# FINAL_YEAR_PROJECT.net
KiCad netlist of a schematic drawn in EasyEDA
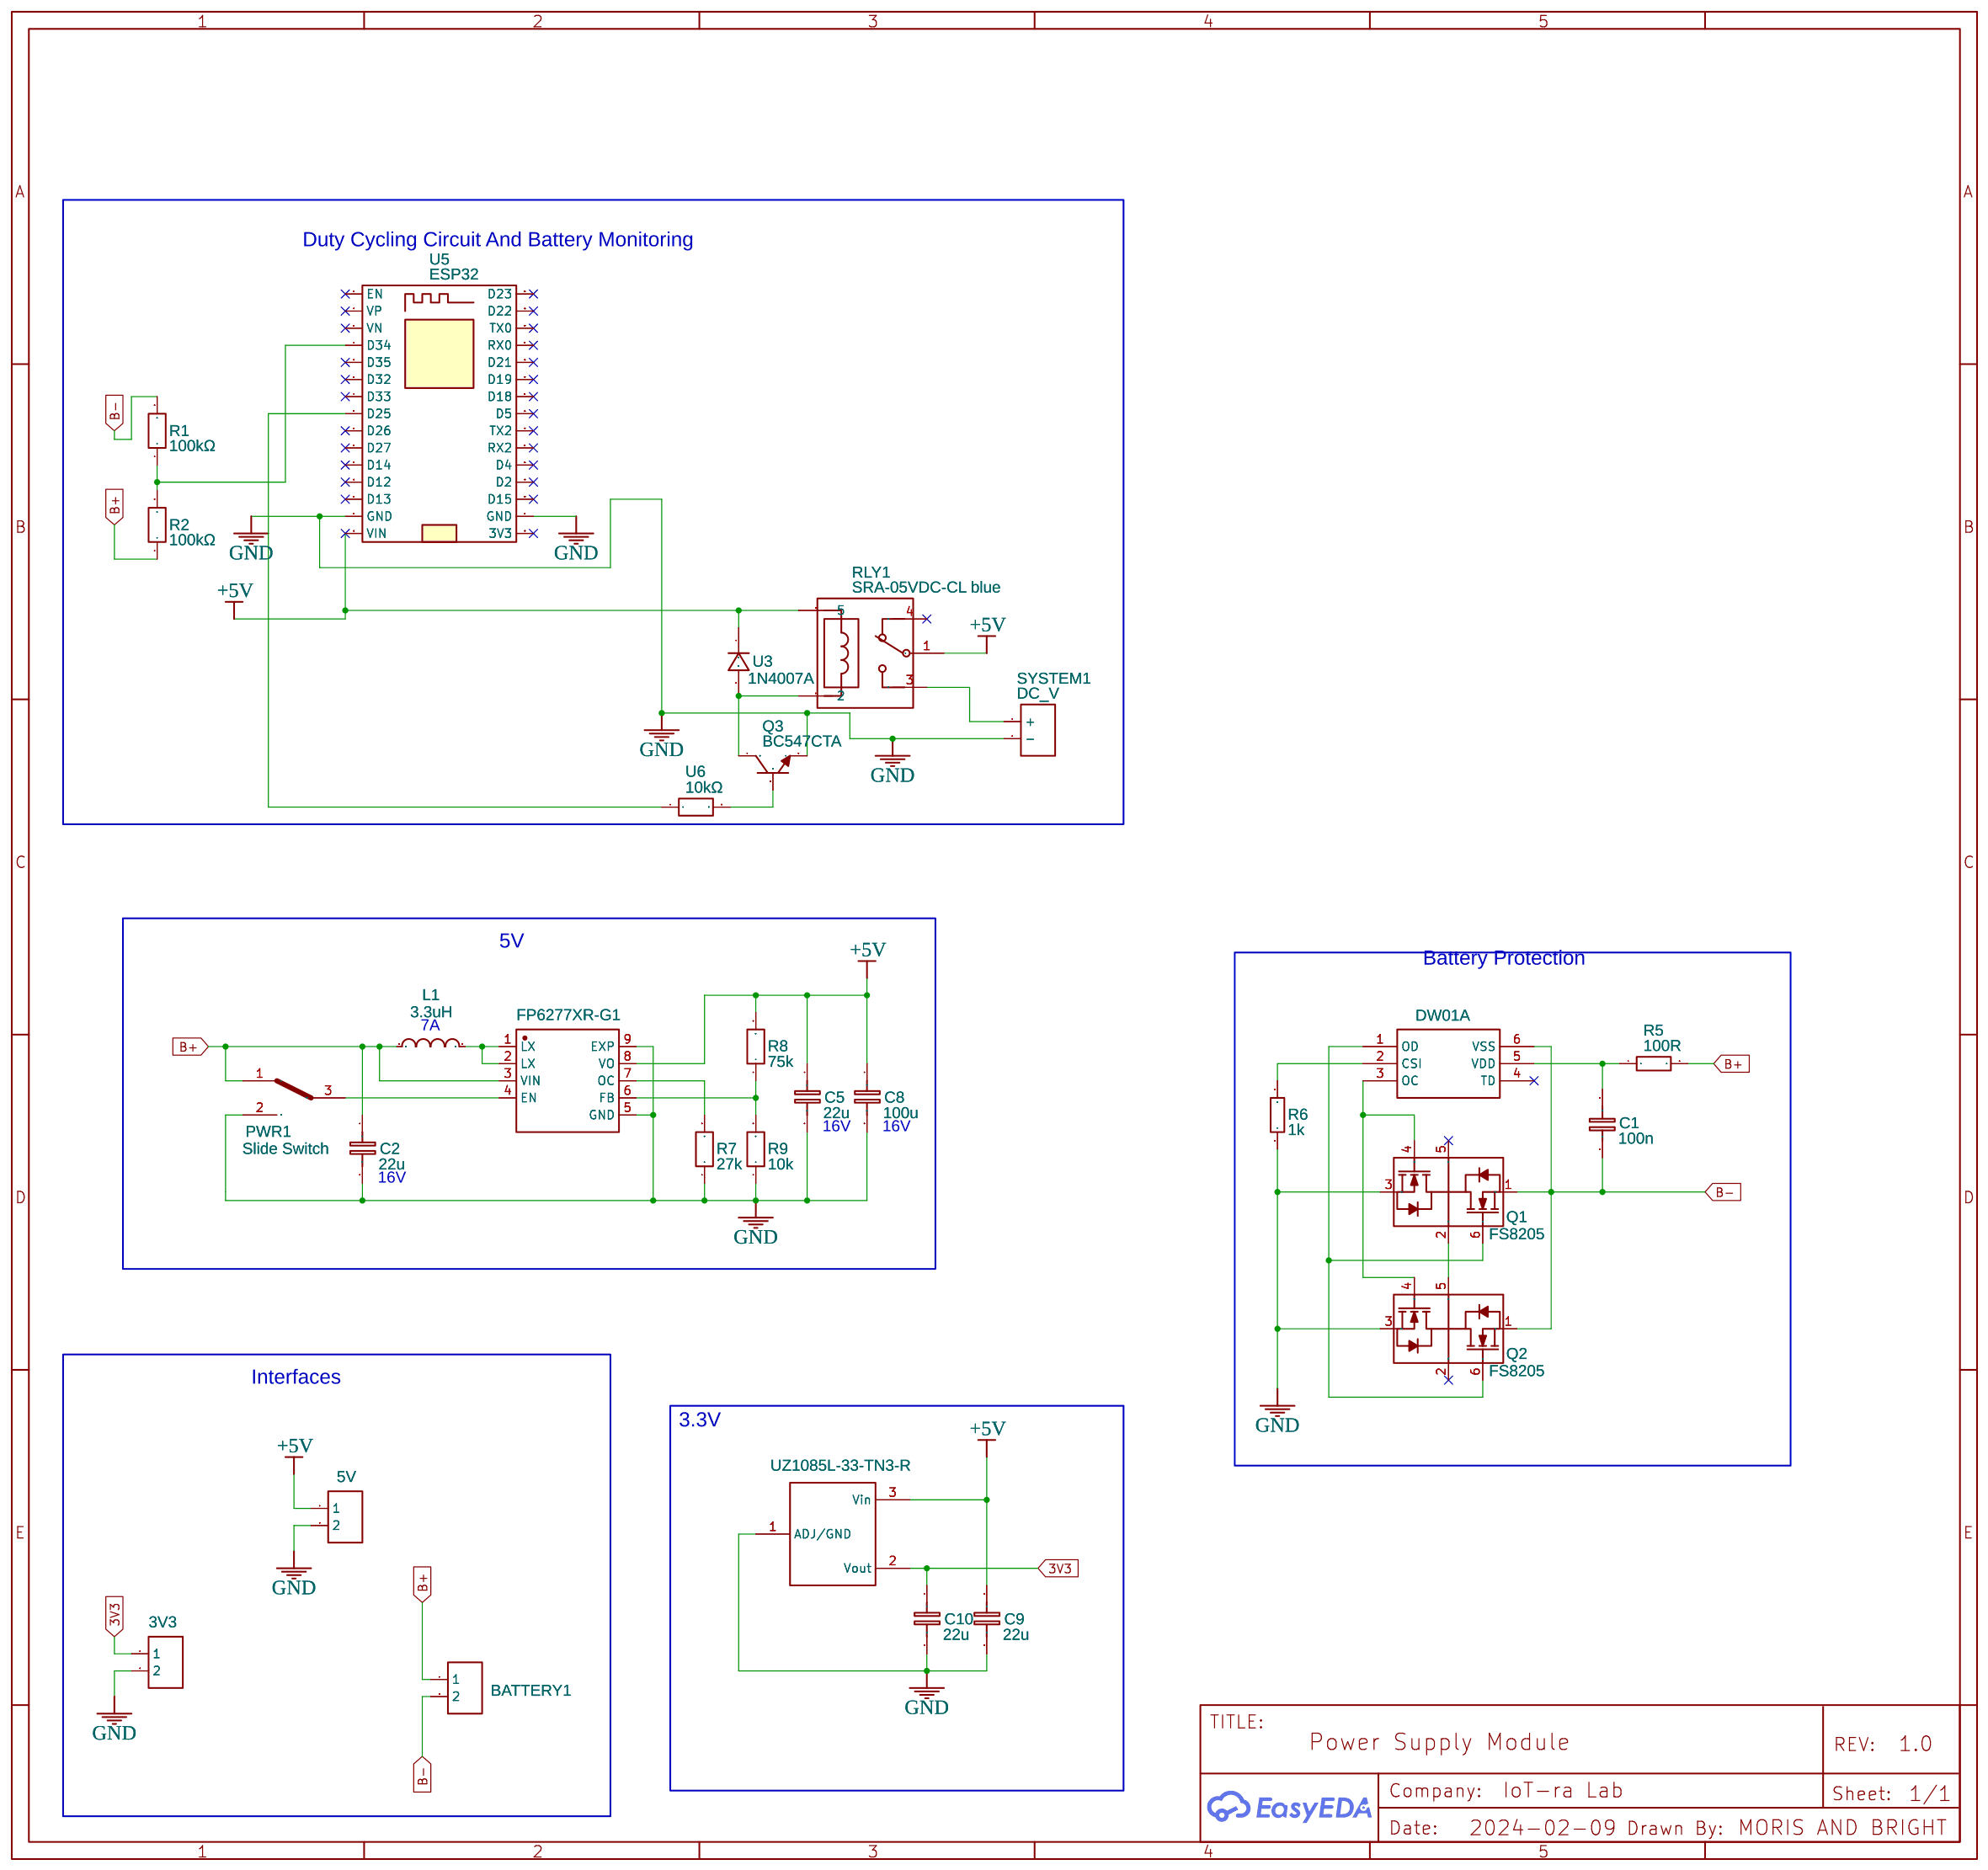
[diagram p0: schematic sheet]

(export (version "E")
  (design (tool "Eeschema 10.0.6"))
  (components
    (comp (ref "3V3")
      (value "Connector")
      (fields (field (name "Manufacturer Part") "2.54-1*2PFemale") (field (name "Manufacturer") "BOOMELE"))
      (libsource (lib "") (part "Unknown_80_-110"))
    )
    (comp (ref "5V")
      (value "Connector")
      (fields (field (name "Manufacturer Part") "2.54-1*2PFemale") (field (name "Manufacturer") "BOOMELE"))
      (libsource (lib "") (part "Unknown_185_-195"))
    )
    (comp (ref "BATTERY1")
      (value "Connector")
      (fields (field (name "Manufacturer Part") "2.54-1*2PFemale") (field (name "Manufacturer") "BOOMELE"))
      (libsource (lib "") (part "Unknown_255_-95"))
    )
    (comp (ref "C1")
      (value "100n")
      (fields (field (name "Manufacturer Part") "CC0805KRX7R9BB104") (field (name "Manufacturer") "YAGEO"))
      (libsource (lib "") (part "Cap_0805_EU_2"))
    )
    (comp (ref "C2")
      (value "22u")
      (fields (field (name "Manufacturer Part") "CL21A226MAQNNNE") (field (name "Manufacturer") "SAMSUNG"))
      (libsource (lib "") (part "Cap_0805_EU"))
    )
    (comp (ref "C5")
      (value "22u")
      (fields (field (name "Manufacturer Part") "CL21A226MAQNNNE") (field (name "Manufacturer") "SAMSUNG"))
      (libsource (lib "") (part "Cap_0805_EU"))
    )
    (comp (ref "C8")
      (value "100u")
      (fields (field (name "Manufacturer Part") "CL31A107MPHNNNE") (field (name "Manufacturer") "SAMSUNG"))
      (libsource (lib "") (part "Cap_0805_EU"))
    )
    (comp (ref "C9")
      (value "22u")
      (fields (field (name "Manufacturer Part") "CL21A226MAQNNNE") (field (name "Manufacturer") "SAMSUNG"))
      (libsource (lib "") (part "Cap_0805_EU_1"))
    )
    (comp (ref "C10")
      (value "22u")
      (fields (field (name "Manufacturer Part") "CL21A226MAQNNNE") (field (name "Manufacturer") "SAMSUNG"))
      (libsource (lib "") (part "Cap_0805_EU_1"))
    )
    (comp (ref "L1")
      (value "3.3uH")
      (fields (field (name "Manufacturer Part") "JSHC0650H-3R3M-G") (field (name "Manufacturer") "Jinlai"))
      (libsource (lib "") (part "JSHC0650H-3R3M-G"))
    )
    (comp (ref "PWR1")
      (value "Slide Switch")
      (fields (field (name "Manufacturer Part") "New SchematicLib"))
      (libsource (lib "") (part "Unknown_160_-440"))
    )
    (comp (ref "Q1")
      (value "FS8205")
      (fields (field (name "Manufacturer") "FORTUNE"))
      (libsource (lib "") (part "FS8205"))
    )
    (comp (ref "Q2")
      (value "FS8205")
      (fields (field (name "Manufacturer") "FORTUNE"))
      (libsource (lib "") (part "FS8205"))
    )
    (comp (ref "Q3")
      (value "BC547CTA")
      (fields (field (name "Manufacturer") "onsemi(安森美)"))
      (libsource (lib "") (part "BC547CTA"))
    )
    (comp (ref "R1")
      (value "100kΩ")
      (fields
        (field (name "Manufacturer Part") "RNF14FAE100K")
        (field (name "Manufacturer") "SEI(Stackpole Electronics Inc.)")
      )
      (libsource (lib "") (part "RNF14FAE100K"))
    )
    (comp (ref "R2")
      (value "100kΩ")
      (fields
        (field (name "Manufacturer Part") "RNF14FAE100K")
        (field (name "Manufacturer") "SEI(Stackpole Electronics Inc.)")
      )
      (libsource (lib "") (part "RNF14FAE100K"))
    )
    (comp (ref "R5")
      (value "100R")
      (fields (field (name "Manufacturer Part") "0805W8F1000T5E") (field (name "Manufacturer") "UniOhm"))
      (libsource (lib "") (part "Res_0805(1/8W)_EU_2"))
    )
    (comp (ref "R6")
      (value "1k")
      (fields (field (name "Manufacturer Part") "0805W8F1001T5E") (field (name "Manufacturer") "UniOhm"))
      (libsource (lib "") (part "Res_0805(1/8W)_EU_1"))
    )
    (comp (ref "R7")
      (value "27k")
      (fields (field (name "Manufacturer Part") "0805W8F2702T5E") (field (name "Manufacturer") "UniOhm"))
      (libsource (lib "") (part "Res_0805(1/8W)_EU"))
    )
    (comp (ref "R8")
      (value "75k")
      (fields (field (name "Manufacturer Part") "0805W8F7502T5E") (field (name "Manufacturer") "UniOhm"))
      (libsource (lib "") (part "Res_0805(1/8W)_EU"))
    )
    (comp (ref "R9")
      (value "10k")
      (fields (field (name "Manufacturer Part") "0805W8F1002T5E") (field (name "Manufacturer") "UniOhm"))
      (libsource (lib "") (part "Res_0805(1/8W)_EU"))
    )
    (comp (ref "RLY1")
      (value "SRA-05VDC-CL blue")
      (fields (field (name "Manufacturer Part") "SRA-05VDC-CL") (field (name "Manufacturer") "松乐"))
      (libsource (lib "") (part "SRA-05VDC-CL blue"))
    )
    (comp (ref "SYSTEM1") (value "DC_V") (libsource (lib "") (part "DC_V")))
    (comp (ref "U1")
      (value "FP6277XR-G1")
      (fields (field (name "Manufacturer") "Feeling Technology"))
      (libsource (lib "") (part "FP6277XR-G1"))
    )
    (comp (ref "U2")
      (value "DW01A")
      (fields (field (name "Manufacturer") "FM"))
      (libsource (lib "") (part "Unknown_835_-460"))
    )
    (comp (ref "U3")
      (value "1N4007A")
      (fields (field (name "Manufacturer") "LRC(乐山无线电)"))
      (libsource (lib "") (part "1N4007A"))
    )
    (comp (ref "U4")
      (value "UZ1085L-33-TN3-R")
      (fields (field (name "Manufacturer") "UTC"))
      (libsource (lib "") (part "UZ1085L-33-TN3-R"))
    )
    (comp (ref "U5") (value "ESP32") (libsource (lib "") (part "ESP32")))
    (comp (ref "U6")
      (value "10kΩ")
      (fields (field (name "Manufacturer Part") "FM0207FTE52-10K") (field (name "Manufacturer") "YAGEO(国巨)"))
      (libsource (lib "") (part "FM0207FTE52-10K"))
    )
  )
  (nets
    (net (code "1") (name "+5V") (class "Default")
      (node (ref "5V") (pin "1") (pinfunction "1_1") (pintype "input"))
      (node (ref "C5") (pin "1") (pinfunction "1_1") (pintype "unspecified"))
      (node (ref "C8") (pin "1") (pinfunction "1_1") (pintype "unspecified"))
      (node (ref "C9") (pin "1") (pinfunction "1_1") (pintype "unspecified"))
      (node (ref "R8") (pin "2") (pinfunction "2_2") (pintype "unspecified"))
      (node (ref "RLY1") (pin "1") (pinfunction "1_1") (pintype "unspecified"))
      (node (ref "RLY1") (pin "5") (pinfunction "5_5") (pintype "unspecified"))
      (node (ref "U1") (pin "8") (pinfunction "VO_8") (pintype "unspecified"))
      (node (ref "U3") (pin "1") (pinfunction "1_1") (pintype "unspecified"))
      (node (ref "U4") (pin "3") (pinfunction "Vin_3") (pintype "unspecified"))
      (node (ref "U5") (pin "15") (pinfunction "VIN_15") (pintype "unspecified"))
    )
    (net (code "2") (name "3V3") (class "Default")
      (node (ref "3V3") (pin "1") (pinfunction "1_1") (pintype "input"))
      (node (ref "C10") (pin "1") (pinfunction "1_1") (pintype "unspecified"))
      (node (ref "U4") (pin "2") (pinfunction "Vout_2") (pintype "unspecified"))
    )
    (net (code "3") (name "B+") (class "Default")
      (node (ref "BATTERY1") (pin "1") (pinfunction "1_1") (pintype "input"))
      (node (ref "C2") (pin "1") (pinfunction "1_1") (pintype "unspecified"))
      (node (ref "L1") (pin "1") (pinfunction "1_1") (pintype "unspecified"))
      (node (ref "PWR1") (pin "1") (pinfunction "1_1") (pintype "unspecified"))
      (node (ref "R2") (pin "1") (pinfunction "1_1") (pintype "unspecified"))
      (node (ref "R5") (pin "2") (pinfunction "2_2") (pintype "unspecified"))
      (node (ref "U1") (pin "3") (pinfunction "VIN_3") (pintype "unspecified"))
    )
    (net (code "4") (name "B-") (class "Default")
      (node (ref "BATTERY1") (pin "2") (pinfunction "2_2") (pintype "input"))
      (node (ref "C1") (pin "1") (pinfunction "1_1") (pintype "unspecified"))
      (node (ref "Q1") (pin "1") (pinfunction "S1_1") (pintype "unspecified"))
      (node (ref "Q2") (pin "1") (pinfunction "S1_1") (pintype "unspecified"))
      (node (ref "R1") (pin "2") (pinfunction "2_2") (pintype "unspecified"))
      (node (ref "U2") (pin "6") (pinfunction "VSS_6") (pintype "unspecified"))
    )
    (net (code "5") (name "GND") (class "Default")
      (node (ref "3V3") (pin "2") (pinfunction "2_2") (pintype "input"))
      (node (ref "5V") (pin "2") (pinfunction "2_2") (pintype "input"))
      (node (ref "C10") (pin "2") (pinfunction "2_2") (pintype "unspecified"))
      (node (ref "C2") (pin "2") (pinfunction "2_2") (pintype "unspecified"))
      (node (ref "C5") (pin "2") (pinfunction "2_2") (pintype "unspecified"))
      (node (ref "C8") (pin "2") (pinfunction "2_2") (pintype "unspecified"))
      (node (ref "C9") (pin "2") (pinfunction "2_2") (pintype "unspecified"))
      (node (ref "PWR1") (pin "2") (pinfunction "2_2") (pintype "unspecified"))
      (node (ref "Q1") (pin "3") (pinfunction "S2_3") (pintype "unspecified"))
      (node (ref "Q2") (pin "3") (pinfunction "S2_3") (pintype "unspecified"))
      (node (ref "Q3") (pin "3") (pinfunction "E_3") (pintype "input"))
      (node (ref "R6") (pin "1") (pinfunction "1_1") (pintype "unspecified"))
      (node (ref "R7") (pin "1") (pinfunction "1_1") (pintype "unspecified"))
      (node (ref "R9") (pin "1") (pinfunction "1_1") (pintype "unspecified"))
      (node (ref "SYSTEM1") (pin "2") (pinfunction "-_2") (pintype "unspecified"))
      (node (ref "U1") (pin "5") (pinfunction "GND_5") (pintype "unspecified"))
      (node (ref "U1") (pin "9") (pinfunction "EXP_9") (pintype "unspecified"))
      (node (ref "U4") (pin "1") (pinfunction "ADJ/GND_1") (pintype "unspecified"))
      (node (ref "U5") (pin "14") (pinfunction "GND_14") (pintype "unspecified"))
      (node (ref "U5") (pin "17") (pinfunction "GND_17") (pintype "unspecified"))
    )
    (net (code "6") (name "Net-(L1-Pad2)") (class "Default")
      (node (ref "L1") (pin "2") (pinfunction "2_2") (pintype "unspecified"))
      (node (ref "U1") (pin "1") (pinfunction "LX_1") (pintype "unspecified"))
      (node (ref "U1") (pin "2") (pinfunction "LX_2") (pintype "unspecified"))
    )
    (net (code "7") (name "Net-(Q1-D12-Pad2)") (class "Default")
      (node (ref "Q1") (pin "2") (pinfunction "D12_2") (pintype "unspecified"))
      (node (ref "Q2") (pin "5") (pinfunction "D12_5") (pintype "unspecified"))
    )
    (net (code "8") (name "Net-(Q1-G1)") (class "Default")
      (node (ref "Q1") (pin "6") (pinfunction "G1_6") (pintype "unspecified"))
      (node (ref "Q2") (pin "6") (pinfunction "G1_6") (pintype "unspecified"))
      (node (ref "U2") (pin "1") (pinfunction "OD_1") (pintype "unspecified"))
    )
    (net (code "9") (name "Net-(Q1-G2)") (class "Default")
      (node (ref "Q1") (pin "4") (pinfunction "G2_4") (pintype "unspecified"))
      (node (ref "Q2") (pin "4") (pinfunction "G2_4") (pintype "unspecified"))
      (node (ref "U2") (pin "3") (pinfunction "OC_3") (pintype "unspecified"))
    )
    (net (code "10") (name "Net-(Q3-B)") (class "Default")
      (node (ref "Q3") (pin "2") (pinfunction "B_2") (pintype "input"))
      (node (ref "U6") (pin "2") (pinfunction "2_2") (pintype "unspecified"))
    )
    (net (code "11") (name "Net-(Q3-C)") (class "Default")
      (node (ref "Q3") (pin "1") (pinfunction "C_1") (pintype "input"))
      (node (ref "RLY1") (pin "2") (pinfunction "2_2") (pintype "unspecified"))
      (node (ref "U3") (pin "2") (pinfunction "2_2") (pintype "unspecified"))
    )
    (net (code "12") (name "Net-(SYSTEM1-+)") (class "Default")
      (node (ref "RLY1") (pin "3") (pinfunction "3_3") (pintype "unspecified"))
      (node (ref "SYSTEM1") (pin "1") (pinfunction "+_1") (pintype "unspecified"))
    )
    (net (code "13") (name "Net-(U1-EN)") (class "Default")
      (node (ref "PWR1") (pin "3") (pinfunction "3_3") (pintype "unspecified"))
      (node (ref "U1") (pin "4") (pinfunction "EN_4") (pintype "unspecified"))
    )
    (net (code "14") (name "Net-(U1-FB)") (class "Default")
      (node (ref "R8") (pin "1") (pinfunction "1_1") (pintype "unspecified"))
      (node (ref "R9") (pin "2") (pinfunction "2_2") (pintype "unspecified"))
      (node (ref "U1") (pin "6") (pinfunction "FB_6") (pintype "unspecified"))
    )
    (net (code "15") (name "Net-(U1-OC)") (class "Default")
      (node (ref "R7") (pin "2") (pinfunction "2_2") (pintype "unspecified"))
      (node (ref "U1") (pin "7") (pinfunction "OC_7") (pintype "unspecified"))
    )
    (net (code "16") (name "Net-(U2-CSI)") (class "Default")
      (node (ref "R6") (pin "2") (pinfunction "2_2") (pintype "unspecified"))
      (node (ref "U2") (pin "2") (pinfunction "CSI_2") (pintype "unspecified"))
    )
    (net (code "17") (name "Net-(U2-VDD)") (class "Default")
      (node (ref "C1") (pin "2") (pinfunction "2_2") (pintype "unspecified"))
      (node (ref "R5") (pin "1") (pinfunction "1_1") (pintype "unspecified"))
      (node (ref "U2") (pin "5") (pinfunction "VDD_5") (pintype "unspecified"))
    )
    (net (code "18") (name "Net-(U5-D25)") (class "Default")
      (node (ref "U5") (pin "8") (pinfunction "D25_8") (pintype "unspecified"))
      (node (ref "U6") (pin "1") (pinfunction "1_1") (pintype "unspecified"))
    )
    (net (code "19") (name "Net-(U5-D34)") (class "Default")
      (node (ref "R1") (pin "1") (pinfunction "1_1") (pintype "unspecified"))
      (node (ref "R2") (pin "2") (pinfunction "2_2") (pintype "unspecified"))
      (node (ref "U5") (pin "4") (pinfunction "D34_4") (pintype "unspecified"))
    )
    (net (code "20") (name "unconnected-(Q1-D12-Pad5)") (class "Default")
      (node (ref "Q1") (pin "5") (pinfunction "D12_5") (pintype "unspecified+no_connect"))
    )
    (net (code "21") (name "unconnected-(Q2-D12-Pad2)") (class "Default")
      (node (ref "Q2") (pin "2") (pinfunction "D12_2") (pintype "unspecified+no_connect"))
    )
    (net (code "22") (name "unconnected-(RLY1-Pad4)") (class "Default")
      (node (ref "RLY1") (pin "4") (pinfunction "4_4") (pintype "unspecified+no_connect"))
    )
    (net (code "23") (name "unconnected-(U2-TD-Pad4)") (class "Default")
      (node (ref "U2") (pin "4") (pinfunction "TD_4") (pintype "unspecified+no_connect"))
    )
    (net (code "24") (name "unconnected-(U5-3V3-Pad16)") (class "Default")
      (node (ref "U5") (pin "16") (pinfunction "3V3_16") (pintype "unspecified+no_connect"))
    )
    (net (code "25") (name "unconnected-(U5-D2-Pad19)") (class "Default")
      (node (ref "U5") (pin "19") (pinfunction "D2_19") (pintype "unspecified+no_connect"))
    )
    (net (code "26") (name "unconnected-(U5-D4-Pad20)") (class "Default")
      (node (ref "U5") (pin "20") (pinfunction "D4_20") (pintype "unspecified+no_connect"))
    )
    (net (code "27") (name "unconnected-(U5-D5-Pad23)") (class "Default")
      (node (ref "U5") (pin "23") (pinfunction "D5_23") (pintype "unspecified+no_connect"))
    )
    (net (code "28") (name "unconnected-(U5-D12-Pad12)") (class "Default")
      (node (ref "U5") (pin "12") (pinfunction "D12_12") (pintype "unspecified+no_connect"))
    )
    (net (code "29") (name "unconnected-(U5-D13-Pad13)") (class "Default")
      (node (ref "U5") (pin "13") (pinfunction "D13_13") (pintype "unspecified+no_connect"))
    )
    (net (code "30") (name "unconnected-(U5-D14-Pad11)") (class "Default")
      (node (ref "U5") (pin "11") (pinfunction "D14_11") (pintype "unspecified+no_connect"))
    )
    (net (code "31") (name "unconnected-(U5-D15-Pad18)") (class "Default")
      (node (ref "U5") (pin "18") (pinfunction "D15_18") (pintype "unspecified+no_connect"))
    )
    (net (code "32") (name "unconnected-(U5-D18-Pad24)") (class "Default")
      (node (ref "U5") (pin "24") (pinfunction "D18_24") (pintype "unspecified+no_connect"))
    )
    (net (code "33") (name "unconnected-(U5-D19-Pad25)") (class "Default")
      (node (ref "U5") (pin "25") (pinfunction "D19_25") (pintype "unspecified+no_connect"))
    )
    (net (code "34") (name "unconnected-(U5-D21-Pad26)") (class "Default")
      (node (ref "U5") (pin "26") (pinfunction "D21_26") (pintype "unspecified+no_connect"))
    )
    (net (code "35") (name "unconnected-(U5-D22-Pad29)") (class "Default")
      (node (ref "U5") (pin "29") (pinfunction "D22_29") (pintype "unspecified+no_connect"))
    )
    (net (code "36") (name "unconnected-(U5-D23-Pad30)") (class "Default")
      (node (ref "U5") (pin "30") (pinfunction "D23_30") (pintype "unspecified+no_connect"))
    )
    (net (code "37") (name "unconnected-(U5-D26-Pad9)") (class "Default")
      (node (ref "U5") (pin "9") (pinfunction "D26_9") (pintype "unspecified+no_connect"))
    )
    (net (code "38") (name "unconnected-(U5-D27-Pad10)") (class "Default")
      (node (ref "U5") (pin "10") (pinfunction "D27_10") (pintype "unspecified+no_connect"))
    )
    (net (code "39") (name "unconnected-(U5-D32-Pad6)") (class "Default")
      (node (ref "U5") (pin "6") (pinfunction "D32_6") (pintype "unspecified+no_connect"))
    )
    (net (code "40") (name "unconnected-(U5-D33-Pad7)") (class "Default")
      (node (ref "U5") (pin "7") (pinfunction "D33_7") (pintype "unspecified+no_connect"))
    )
    (net (code "41") (name "unconnected-(U5-D35-Pad5)") (class "Default")
      (node (ref "U5") (pin "5") (pinfunction "D35_5") (pintype "unspecified+no_connect"))
    )
    (net (code "42") (name "unconnected-(U5-EN-Pad1)") (class "Default")
      (node (ref "U5") (pin "1") (pinfunction "EN_1") (pintype "unspecified+no_connect"))
    )
    (net (code "43") (name "unconnected-(U5-RX0-Pad27)") (class "Default")
      (node (ref "U5") (pin "27") (pinfunction "RX0_27") (pintype "unspecified+no_connect"))
    )
    (net (code "44") (name "unconnected-(U5-RX2-Pad21)") (class "Default")
      (node (ref "U5") (pin "21") (pinfunction "RX2_21") (pintype "unspecified+no_connect"))
    )
    (net (code "45") (name "unconnected-(U5-TX0-Pad28)") (class "Default")
      (node (ref "U5") (pin "28") (pinfunction "TX0_28") (pintype "unspecified+no_connect"))
    )
    (net (code "46") (name "unconnected-(U5-TX2-Pad22)") (class "Default")
      (node (ref "U5") (pin "22") (pinfunction "TX2_22") (pintype "unspecified+no_connect"))
    )
    (net (code "47") (name "unconnected-(U5-VN-Pad3)") (class "Default")
      (node (ref "U5") (pin "3") (pinfunction "VN_3") (pintype "unspecified+no_connect"))
    )
    (net (code "48") (name "unconnected-(U5-VP-Pad2)") (class "Default")
      (node (ref "U5") (pin "2") (pinfunction "VP_2") (pintype "unspecified+no_connect"))
    )
  )
)
